# BBBBoat-cape.net
KiCad netlist of a schematic drawn in EAGLE
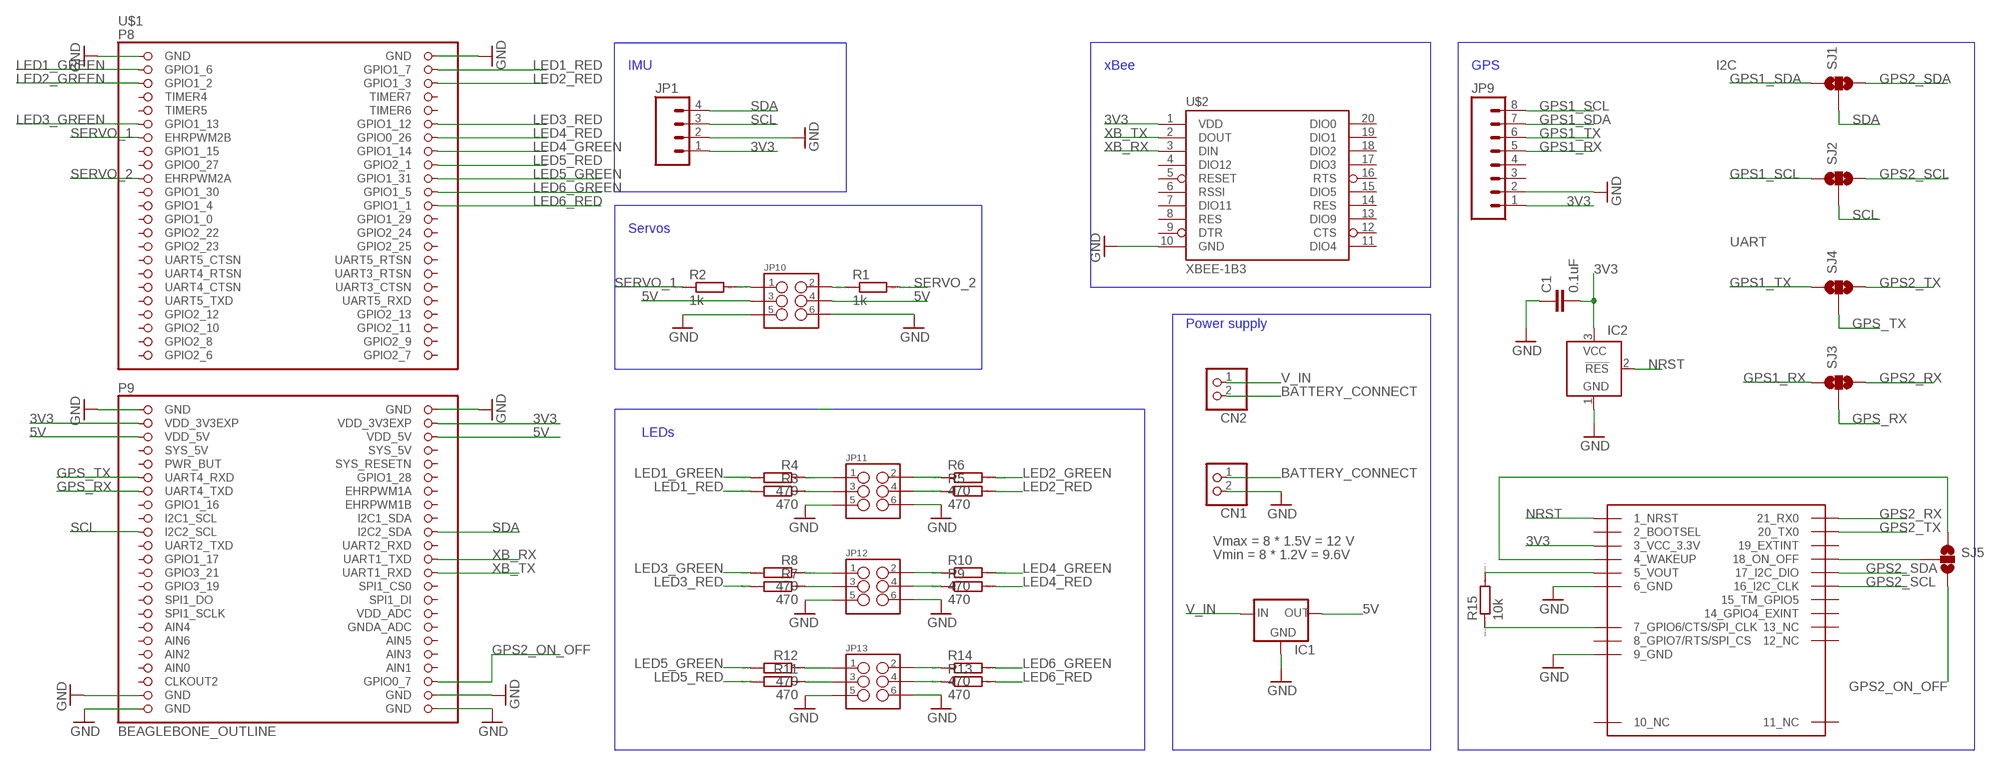
[diagram p0: schematic, sheet 1]

(export (version "E")
  (design (tool "Eeschema 10.0.6"))
  (components
    (comp (ref "C1")
      (value "0.1uF")
      (footprint "eagle-import:0603-CAP")
      (libsource (lib "eagle-import") (part "0.1UF-25V-5%(0603)"))
    )
    (comp (ref "CN1")
      (value "JST_2PIN-SMT")
      (footprint "eagle-import:JST-PH-2-SMT")
      (libsource (lib "eagle-import") (part "JST_2PIN-SMT"))
    )
    (comp (ref "CN2")
      (value "JST_2PIN-SMT")
      (footprint "eagle-import:JST-PH-2-SMT")
      (libsource (lib "eagle-import") (part "JST_2PIN-SMT"))
    )
    (comp (ref "IC1")
      (value "V_REG_78XX-TO-220")
      (footprint "eagle-import:TO-220-ALT")
      (libsource (lib "eagle-import") (part "V_REG_78XX-TO-220"))
    )
    (comp (ref "IC2")
      (value "TCM809")
      (footprint "eagle-import:SOT23B-3")
      (fields (field (name "MF") "MICROCHIP") (field (name "MPN") "TCM809MENB713"))
      (libsource (lib "eagle-import") (part "TCM809"))
    )
    (comp (ref "JP1")
      (value "M04SMD_STRAIGHT_COMBO")
      (footprint "eagle-import:1X04_SMD_STRAIGHT_COMBO")
      (libsource (lib "eagle-import") (part "M04SMD_STRAIGHT_COMBO"))
    )
    (comp (ref "JP9")
      (value "M08SMD-MALE")
      (footprint "eagle-import:1X08_SMD_MALE")
      (libsource (lib "eagle-import") (part "M08SMD-MALE"))
    )
    (comp (ref "JP10")
      (value "M03X2")
      (footprint "eagle-import:2X3_SMD")
      (libsource (lib "eagle-import") (part "M03X2"))
    )
    (comp (ref "JP11")
      (value "M03X2")
      (footprint "eagle-import:2X3_SMD")
      (libsource (lib "eagle-import") (part "M03X2"))
    )
    (comp (ref "JP12")
      (value "M03X2")
      (footprint "eagle-import:2X3_SMD")
      (libsource (lib "eagle-import") (part "M03X2"))
    )
    (comp (ref "JP13")
      (value "M03X2")
      (footprint "eagle-import:2X3_SMD")
      (libsource (lib "eagle-import") (part "M03X2"))
    )
    (comp (ref "R1")
      (value "1k")
      (footprint "eagle-import:0204_7")
      (libsource (lib "eagle-import") (part "R0204/7"))
    )
    (comp (ref "R2")
      (value "1k")
      (footprint "eagle-import:0204_7")
      (libsource (lib "eagle-import") (part "R0204/7"))
    )
    (comp (ref "R3")
      (value "470")
      (footprint "eagle-import:0204_7")
      (libsource (lib "eagle-import") (part "R0204/7"))
    )
    (comp (ref "R4")
      (value "470")
      (footprint "eagle-import:0204_7")
      (libsource (lib "eagle-import") (part "R0204/7"))
    )
    (comp (ref "R5")
      (value "470")
      (footprint "eagle-import:0204_7")
      (libsource (lib "eagle-import") (part "R0204/7"))
    )
    (comp (ref "R6")
      (value "470")
      (footprint "eagle-import:0204_7")
      (libsource (lib "eagle-import") (part "R0204/7"))
    )
    (comp (ref "R7")
      (value "470")
      (footprint "eagle-import:0204_7")
      (libsource (lib "eagle-import") (part "R0204/7"))
    )
    (comp (ref "R8")
      (value "470")
      (footprint "eagle-import:0204_7")
      (libsource (lib "eagle-import") (part "R0204/7"))
    )
    (comp (ref "R9")
      (value "470")
      (footprint "eagle-import:0204_7")
      (libsource (lib "eagle-import") (part "R0204/7"))
    )
    (comp (ref "R10")
      (value "470")
      (footprint "eagle-import:0204_7")
      (libsource (lib "eagle-import") (part "R0204/7"))
    )
    (comp (ref "R11")
      (value "470")
      (footprint "eagle-import:0204_7")
      (libsource (lib "eagle-import") (part "R0204/7"))
    )
    (comp (ref "R12")
      (value "470")
      (footprint "eagle-import:0204_7")
      (libsource (lib "eagle-import") (part "R0204/7"))
    )
    (comp (ref "R13")
      (value "470")
      (footprint "eagle-import:0204_7")
      (libsource (lib "eagle-import") (part "R0204/7"))
    )
    (comp (ref "R14")
      (value "470")
      (footprint "eagle-import:0204_7")
      (libsource (lib "eagle-import") (part "R0204/7"))
    )
    (comp (ref "R15")
      (value "10k")
      (footprint "eagle-import:0204_7")
      (libsource (lib "eagle-import") (part "R0204/7"))
    )
    (comp (ref "SJ1")
      (value "SOLDERJUMPER_2WAYT")
      (footprint "eagle-import:SJ_2")
      (libsource (lib "eagle-import") (part "SOLDERJUMPER_2WAYT"))
    )
    (comp (ref "SJ2")
      (value "SOLDERJUMPER_2WAYT")
      (footprint "eagle-import:SJ_2")
      (libsource (lib "eagle-import") (part "SOLDERJUMPER_2WAYT"))
    )
    (comp (ref "SJ3")
      (value "SOLDERJUMPER_2WAYT")
      (footprint "eagle-import:SJ_2")
      (libsource (lib "eagle-import") (part "SOLDERJUMPER_2WAYT"))
    )
    (comp (ref "SJ4")
      (value "SOLDERJUMPER_2WAYT")
      (footprint "eagle-import:SJ_2")
      (libsource (lib "eagle-import") (part "SOLDERJUMPER_2WAYT"))
    )
    (comp (ref "SJ5")
      (value "SOLDERJUMPER_2WAYT")
      (footprint "eagle-import:SJ_2")
      (libsource (lib "eagle-import") (part "SOLDERJUMPER_2WAYT"))
    )
    (comp (ref "U$1")
      (value "BEAGLEBONE_OUTLINE")
      (footprint "eagle-import:BEAGLEBONE_SHIELD")
      (libsource (lib "eagle-import") (part "BEAGLEBONE_OUTLINE"))
    )
    (comp (ref "U$2")
      (value "XBEE-1B3")
      (footprint "eagle-import:XBEE-SMD")
      (libsource (lib "eagle-import") (part "XBEE-1B3"))
    )
    (comp (ref "U$3")
      (value "A2035-H")
      (footprint "eagle-import:A2035H")
      (libsource (lib "eagle-import") (part "A2035-H"))
    )
  )
  (nets
    (net (code "1") (name "/3V3") (class "Default")
      (node (ref "C1") (pin "2") (pinfunction "2_2") (pintype "passive"))
      (node (ref "IC2") (pin "3") (pinfunction "VCC_3") (pintype "power_in"))
      (node (ref "JP1") (pin "1") (pinfunction "1_1") (pintype "passive"))
      (node (ref "JP9") (pin "1") (pinfunction "1_1") (pintype "passive"))
      (node (ref "U$1") (pin "49") (pinfunction "VDD_3V3EXP_49") (pintype "power_in"))
      (node (ref "U$1") (pin "50") (pinfunction "VDD_3V3EXP_50") (pintype "power_in"))
      (node (ref "U$2") (pin "1") (pinfunction "VDD_1") (pintype "power_in"))
      (node (ref "U$3") (pin "3_VCC_3.3V") (pinfunction "3_VCC_3.3V_3_VCC_3.3V") (pintype "bidirectional"))
    )
    (net (code "2") (name "/5V") (class "Default")
      (node (ref "IC1") (pin "OUT") (pinfunction "OUT_OUT") (pintype "output"))
      (node (ref "JP10") (pin "3") (pinfunction "3_3") (pintype "bidirectional"))
      (node (ref "JP10") (pin "4") (pinfunction "4_4") (pintype "bidirectional"))
      (node (ref "U$1") (pin "51") (pinfunction "VDD_5V_51") (pintype "power_in"))
      (node (ref "U$1") (pin "52") (pinfunction "VDD_5V_52") (pintype "power_in"))
    )
    (net (code "3") (name "/AIN0") (class "Default")
      (node (ref "U$1") (pin "85") (pinfunction "AIN0_85") (pintype "power_in"))
    )
    (net (code "4") (name "/BATTERY_CONNECT") (class "Default")
      (node (ref "CN1") (pin "1") (pinfunction "2_1") (pintype "passive"))
      (node (ref "CN2") (pin "2") (pinfunction "1_2") (pintype "passive"))
    )
    (net (code "5") (name "/GPS1_RX") (class "Default")
      (node (ref "JP9") (pin "5") (pinfunction "5_5") (pintype "passive"))
      (node (ref "SJ3") (pin "1") (pinfunction "1_1") (pintype "passive"))
    )
    (net (code "6") (name "/GPS1_SCL") (class "Default")
      (node (ref "JP9") (pin "8") (pinfunction "8_8") (pintype "passive"))
      (node (ref "SJ2") (pin "1") (pinfunction "1_1") (pintype "passive"))
    )
    (net (code "7") (name "/GPS1_SDA") (class "Default")
      (node (ref "JP9") (pin "7") (pinfunction "7_7") (pintype "passive"))
      (node (ref "SJ1") (pin "1") (pinfunction "1_1") (pintype "passive"))
    )
    (net (code "8") (name "/GPS1_TX") (class "Default")
      (node (ref "JP9") (pin "6") (pinfunction "6_6") (pintype "passive"))
      (node (ref "SJ4") (pin "1") (pinfunction "1_1") (pintype "passive"))
    )
    (net (code "9") (name "/GPS2_ON_OFF") (class "Default")
      (node (ref "SJ5") (pin "3") (pinfunction "3_3") (pintype "passive"))
      (node (ref "U$1") (pin "88") (pinfunction "GPIO0_7_88") (pintype "passive"))
    )
    (net (code "10") (name "/GPS2_RX") (class "Default")
      (node (ref "SJ3") (pin "3") (pinfunction "3_3") (pintype "passive"))
      (node (ref "U$3") (pin "21_RX0") (pinfunction "21_RX0_21_RX0") (pintype "bidirectional"))
    )
    (net (code "11") (name "/GPS2_SCL") (class "Default")
      (node (ref "SJ2") (pin "3") (pinfunction "3_3") (pintype "passive"))
      (node (ref "U$3") (pin "16_I2C_CLK") (pinfunction "16_I2C_CLK_16_I2C_CLK") (pintype "bidirectional"))
    )
    (net (code "12") (name "/GPS2_SDA") (class "Default")
      (node (ref "SJ1") (pin "3") (pinfunction "3_3") (pintype "passive"))
      (node (ref "U$3") (pin "17_I2C_DIO") (pinfunction "17_I2C_DIO_17_I2C_DIO") (pintype "bidirectional"))
    )
    (net (code "13") (name "/GPS2_TX") (class "Default")
      (node (ref "SJ4") (pin "3") (pinfunction "3_3") (pintype "passive"))
      (node (ref "U$3") (pin "20_TX0") (pinfunction "20_TX0_20_TX0") (pintype "bidirectional"))
    )
    (net (code "14") (name "/GPS_RX") (class "Default")
      (node (ref "SJ3") (pin "2") (pinfunction "2_2") (pintype "passive"))
      (node (ref "U$1") (pin "59") (pinfunction "UART4_TXD_59") (pintype "passive"))
    )
    (net (code "15") (name "/GPS_TX") (class "Default")
      (node (ref "SJ4") (pin "2") (pinfunction "2_2") (pintype "passive"))
      (node (ref "U$1") (pin "57") (pinfunction "UART4_RXD_57") (pintype "passive"))
    )
    (net (code "16") (name "/LED1_GREEN") (class "Default")
      (node (ref "R4") (pin "2") (pinfunction "2_2") (pintype "passive"))
      (node (ref "U$1") (pin "3") (pinfunction "GPIO1_6_3") (pintype "passive"))
    )
    (net (code "17") (name "/LED1_RED") (class "Default")
      (node (ref "R3") (pin "2") (pinfunction "2_2") (pintype "passive"))
      (node (ref "U$1") (pin "4") (pinfunction "GPIO1_7_4") (pintype "passive"))
    )
    (net (code "18") (name "/LED2_GREEN") (class "Default")
      (node (ref "R6") (pin "2") (pinfunction "2_2") (pintype "passive"))
      (node (ref "U$1") (pin "5") (pinfunction "GPIO1_2_5") (pintype "passive"))
    )
    (net (code "19") (name "/LED2_RED") (class "Default")
      (node (ref "R5") (pin "2") (pinfunction "2_2") (pintype "passive"))
      (node (ref "U$1") (pin "6") (pinfunction "GPIO1_3_6") (pintype "passive"))
    )
    (net (code "20") (name "/LED3_GREEN") (class "Default")
      (node (ref "R8") (pin "2") (pinfunction "2_2") (pintype "passive"))
      (node (ref "U$1") (pin "11") (pinfunction "GPIO1_13_11") (pintype "passive"))
    )
    (net (code "21") (name "/LED3_RED") (class "Default")
      (node (ref "R7") (pin "2") (pinfunction "2_2") (pintype "passive"))
      (node (ref "U$1") (pin "12") (pinfunction "GPIO1_12_12") (pintype "passive"))
    )
    (net (code "22") (name "/LED4_GREEN") (class "Default")
      (node (ref "R10") (pin "2") (pinfunction "2_2") (pintype "passive"))
      (node (ref "U$1") (pin "16") (pinfunction "GPIO1_14_16") (pintype "passive"))
    )
    (net (code "23") (name "/LED4_RED") (class "Default")
      (node (ref "R9") (pin "2") (pinfunction "2_2") (pintype "passive"))
      (node (ref "U$1") (pin "14") (pinfunction "GPIO0_26_14") (pintype "passive"))
    )
    (net (code "24") (name "/LED5_GREEN") (class "Default")
      (node (ref "R12") (pin "2") (pinfunction "2_2") (pintype "passive"))
      (node (ref "U$1") (pin "20") (pinfunction "GPIO1_31_20") (pintype "passive"))
    )
    (net (code "25") (name "/LED5_RED") (class "Default")
      (node (ref "R11") (pin "2") (pinfunction "2_2") (pintype "passive"))
      (node (ref "U$1") (pin "18") (pinfunction "GPIO2_1_18") (pintype "passive"))
    )
    (net (code "26") (name "/LED6_GREEN") (class "Default")
      (node (ref "R14") (pin "2") (pinfunction "2_2") (pintype "passive"))
      (node (ref "U$1") (pin "22") (pinfunction "GPIO1_5_22") (pintype "passive"))
    )
    (net (code "27") (name "/LED6_RED") (class "Default")
      (node (ref "R13") (pin "2") (pinfunction "2_2") (pintype "passive"))
      (node (ref "U$1") (pin "24") (pinfunction "GPIO1_1_24") (pintype "passive"))
    )
    (net (code "28") (name "/NRST") (class "Default")
      (node (ref "IC2") (pin "2") (pinfunction "~{RES}_2") (pintype "output"))
      (node (ref "U$3") (pin "1_NRST") (pinfunction "1_NRST_1_NRST") (pintype "bidirectional"))
    )
    (net (code "29") (name "/SCL") (class "Default")
      (node (ref "JP1") (pin "3") (pinfunction "3_3") (pintype "passive"))
      (node (ref "SJ2") (pin "2") (pinfunction "2_2") (pintype "passive"))
      (node (ref "U$1") (pin "65") (pinfunction "I2C2_SCL_65") (pintype "passive"))
    )
    (net (code "30") (name "/SDA") (class "Default")
      (node (ref "JP1") (pin "4") (pinfunction "4_4") (pintype "passive"))
      (node (ref "SJ1") (pin "2") (pinfunction "2_2") (pintype "passive"))
      (node (ref "U$1") (pin "66") (pinfunction "I2C2_SDA_66") (pintype "passive"))
    )
    (net (code "31") (name "/SERVO_1") (class "Default")
      (node (ref "R2") (pin "1") (pinfunction "1_1") (pintype "passive"))
      (node (ref "U$1") (pin "13") (pinfunction "EHRPWM2B_13") (pintype "passive"))
    )
    (net (code "32") (name "/SERVO_2") (class "Default")
      (node (ref "R1") (pin "2") (pinfunction "2_2") (pintype "passive"))
      (node (ref "U$1") (pin "19") (pinfunction "EHRPWM2A_19") (pintype "passive"))
    )
    (net (code "33") (name "/SYS_5V") (class "Default")
      (node (ref "U$1") (pin "53") (pinfunction "SYS_5V_53") (pintype "power_in"))
    )
    (net (code "34") (name "/V_IN") (class "Default")
      (node (ref "CN2") (pin "1") (pinfunction "2_1") (pintype "passive"))
      (node (ref "IC1") (pin "IN") (pinfunction "IN_IN") (pintype "input"))
    )
    (net (code "35") (name "/XB_RX") (class "Default")
      (node (ref "U$1") (pin "70") (pinfunction "UART1_TXD_70") (pintype "passive"))
      (node (ref "U$2") (pin "3") (pinfunction "DIN_3") (pintype "input"))
    )
    (net (code "36") (name "/XB_TX") (class "Default")
      (node (ref "U$1") (pin "72") (pinfunction "UART1_RXD_72") (pintype "passive"))
      (node (ref "U$2") (pin "2") (pinfunction "DOUT_2") (pintype "output"))
    )
    (net (code "37") (name "GND") (class "Default")
      (node (ref "C1") (pin "1") (pinfunction "1_1") (pintype "passive"))
      (node (ref "CN1") (pin "2") (pinfunction "1_2") (pintype "passive"))
      (node (ref "IC1") (pin "GND") (pinfunction "GND_GND") (pintype "input"))
      (node (ref "IC2") (pin "1") (pinfunction "GND_1") (pintype "power_in"))
      (node (ref "JP1") (pin "2") (pinfunction "2_2") (pintype "passive"))
      (node (ref "JP10") (pin "5") (pinfunction "5_5") (pintype "bidirectional"))
      (node (ref "JP10") (pin "6") (pinfunction "6_6") (pintype "bidirectional"))
      (node (ref "JP11") (pin "5") (pinfunction "5_5") (pintype "bidirectional"))
      (node (ref "JP11") (pin "6") (pinfunction "6_6") (pintype "bidirectional"))
      (node (ref "JP12") (pin "5") (pinfunction "5_5") (pintype "bidirectional"))
      (node (ref "JP12") (pin "6") (pinfunction "6_6") (pintype "bidirectional"))
      (node (ref "JP13") (pin "5") (pinfunction "5_5") (pintype "bidirectional"))
      (node (ref "JP13") (pin "6") (pinfunction "6_6") (pintype "bidirectional"))
      (node (ref "JP9") (pin "2") (pinfunction "2_2") (pintype "passive"))
      (node (ref "U$1") (pin "1") (pinfunction "GND_1") (pintype "power_in"))
      (node (ref "U$1") (pin "2") (pinfunction "GND_2") (pintype "power_in"))
      (node (ref "U$1") (pin "47") (pinfunction "GND_47") (pintype "power_in"))
      (node (ref "U$1") (pin "48") (pinfunction "GND_48") (pintype "power_in"))
      (node (ref "U$1") (pin "89") (pinfunction "GND_89") (pintype "power_in"))
      (node (ref "U$1") (pin "90") (pinfunction "GND_90") (pintype "power_in"))
      (node (ref "U$1") (pin "91") (pinfunction "GND_91") (pintype "power_in"))
      (node (ref "U$1") (pin "92") (pinfunction "GND_92") (pintype "power_in"))
      (node (ref "U$2") (pin "10") (pinfunction "GND_10") (pintype "power_in"))
      (node (ref "U$3") (pin "6_GND") (pinfunction "6_GND_6_GND") (pintype "bidirectional"))
      (node (ref "U$3") (pin "9_GND") (pinfunction "9_GND_9_GND") (pintype "bidirectional"))
    )
    (net (code "38") (name "Net-(JP10-Pad1)") (class "Default")
      (node (ref "JP10") (pin "1") (pinfunction "1_1") (pintype "bidirectional"))
      (node (ref "R2") (pin "2") (pinfunction "2_2") (pintype "passive"))
    )
    (net (code "39") (name "Net-(JP10-Pad2)") (class "Default")
      (node (ref "JP10") (pin "2") (pinfunction "2_2") (pintype "bidirectional"))
      (node (ref "R1") (pin "1") (pinfunction "1_1") (pintype "passive"))
    )
    (net (code "40") (name "Net-(JP11-Pad1)") (class "Default")
      (node (ref "JP11") (pin "1") (pinfunction "1_1") (pintype "bidirectional"))
      (node (ref "R4") (pin "1") (pinfunction "1_1") (pintype "passive"))
    )
    (net (code "41") (name "Net-(JP11-Pad2)") (class "Default")
      (node (ref "JP11") (pin "2") (pinfunction "2_2") (pintype "bidirectional"))
      (node (ref "R6") (pin "1") (pinfunction "1_1") (pintype "passive"))
    )
    (net (code "42") (name "Net-(JP11-Pad3)") (class "Default")
      (node (ref "JP11") (pin "3") (pinfunction "3_3") (pintype "bidirectional"))
      (node (ref "R3") (pin "1") (pinfunction "1_1") (pintype "passive"))
    )
    (net (code "43") (name "Net-(JP11-Pad4)") (class "Default")
      (node (ref "JP11") (pin "4") (pinfunction "4_4") (pintype "bidirectional"))
      (node (ref "R5") (pin "1") (pinfunction "1_1") (pintype "passive"))
    )
    (net (code "44") (name "Net-(JP12-Pad1)") (class "Default")
      (node (ref "JP12") (pin "1") (pinfunction "1_1") (pintype "bidirectional"))
      (node (ref "R8") (pin "1") (pinfunction "1_1") (pintype "passive"))
    )
    (net (code "45") (name "Net-(JP12-Pad2)") (class "Default")
      (node (ref "JP12") (pin "2") (pinfunction "2_2") (pintype "bidirectional"))
      (node (ref "R10") (pin "1") (pinfunction "1_1") (pintype "passive"))
    )
    (net (code "46") (name "Net-(JP12-Pad3)") (class "Default")
      (node (ref "JP12") (pin "3") (pinfunction "3_3") (pintype "bidirectional"))
      (node (ref "R7") (pin "1") (pinfunction "1_1") (pintype "passive"))
    )
    (net (code "47") (name "Net-(JP12-Pad4)") (class "Default")
      (node (ref "JP12") (pin "4") (pinfunction "4_4") (pintype "bidirectional"))
      (node (ref "R9") (pin "1") (pinfunction "1_1") (pintype "passive"))
    )
    (net (code "48") (name "Net-(JP13-Pad1)") (class "Default")
      (node (ref "JP13") (pin "1") (pinfunction "1_1") (pintype "bidirectional"))
      (node (ref "R12") (pin "1") (pinfunction "1_1") (pintype "passive"))
    )
    (net (code "49") (name "Net-(JP13-Pad2)") (class "Default")
      (node (ref "JP13") (pin "2") (pinfunction "2_2") (pintype "bidirectional"))
      (node (ref "R14") (pin "1") (pinfunction "1_1") (pintype "passive"))
    )
    (net (code "50") (name "Net-(JP13-Pad3)") (class "Default")
      (node (ref "JP13") (pin "3") (pinfunction "3_3") (pintype "bidirectional"))
      (node (ref "R11") (pin "1") (pinfunction "1_1") (pintype "passive"))
    )
    (net (code "51") (name "Net-(JP13-Pad4)") (class "Default")
      (node (ref "JP13") (pin "4") (pinfunction "4_4") (pintype "bidirectional"))
      (node (ref "R13") (pin "1") (pinfunction "1_1") (pintype "passive"))
    )
    (net (code "52") (name "Net-(R15-Pad1)") (class "Default")
      (node (ref "R15") (pin "1") (pinfunction "1_1") (pintype "passive"))
      (node (ref "U$3") (pin "7_GPIO6/CTS/SPI_CLK") (pinfunction "7_GPIO6/CTS/SPI_CLK_7_GPIO6/CTS/SPI_CLK") (pintype "bidirectional"))
    )
    (net (code "53") (name "Net-(R15-Pad2)") (class "Default")
      (node (ref "R15") (pin "2") (pinfunction "2_2") (pintype "passive"))
      (node (ref "U$3") (pin "5_VOUT") (pinfunction "5_VOUT_5_VOUT") (pintype "bidirectional"))
    )
    (net (code "54") (name "Net-(SJ5-Pad1)") (class "Default")
      (node (ref "SJ5") (pin "1") (pinfunction "1_1") (pintype "passive"))
      (node (ref "U$3") (pin "4_WAKEUP") (pinfunction "4_WAKEUP_4_WAKEUP") (pintype "bidirectional"))
    )
    (net (code "55") (name "Net-(SJ5-Pad2)") (class "Default")
      (node (ref "SJ5") (pin "2") (pinfunction "2_2") (pintype "passive"))
      (node (ref "U$3") (pin "18_ON_OFF") (pinfunction "18_ON_OFF_18_ON_OFF") (pintype "bidirectional"))
    )
    (net (code "56") (name "unconnected-(JP9-Pad3)") (class "Default")
      (node (ref "JP9") (pin "3") (pinfunction "3_3") (pintype "passive"))
    )
    (net (code "57") (name "unconnected-(JP9-Pad4)") (class "Default")
      (node (ref "JP9") (pin "4") (pinfunction "4_4") (pintype "passive"))
    )
    (net (code "58") (name "unconnected-(U$1-AIN1-Pad86)") (class "Default")
      (node (ref "U$1") (pin "86") (pinfunction "AIN1_86") (pintype "passive"))
    )
    (net (code "59") (name "unconnected-(U$1-AIN2-Pad83)") (class "Default")
      (node (ref "U$1") (pin "83") (pinfunction "AIN2_83") (pintype "passive"))
    )
    (net (code "60") (name "unconnected-(U$1-AIN3-Pad84)") (class "Default")
      (node (ref "U$1") (pin "84") (pinfunction "AIN3_84") (pintype "passive"))
    )
    (net (code "61") (name "unconnected-(U$1-AIN4-Pad79)") (class "Default")
      (node (ref "U$1") (pin "79") (pinfunction "AIN4_79") (pintype "passive"))
    )
    (net (code "62") (name "unconnected-(U$1-AIN5-Pad82)") (class "Default")
      (node (ref "U$1") (pin "82") (pinfunction "AIN5_82") (pintype "passive"))
    )
    (net (code "63") (name "unconnected-(U$1-AIN6-Pad81)") (class "Default")
      (node (ref "U$1") (pin "81") (pinfunction "AIN6_81") (pintype "passive"))
    )
    (net (code "64") (name "unconnected-(U$1-CLKOUT2-Pad87)") (class "Default")
      (node (ref "U$1") (pin "87") (pinfunction "CLKOUT2_87") (pintype "input"))
    )
    (net (code "65") (name "unconnected-(U$1-EHRPWM1A-Pad60)") (class "Default")
      (node (ref "U$1") (pin "60") (pinfunction "EHRPWM1A_60") (pintype "passive"))
    )
    (net (code "66") (name "unconnected-(U$1-EHRPWM1B-Pad62)") (class "Default")
      (node (ref "U$1") (pin "62") (pinfunction "EHRPWM1B_62") (pintype "passive"))
    )
    (net (code "67") (name "unconnected-(U$1-GNDA_ADC-Pad80)") (class "Default")
      (node (ref "U$1") (pin "80") (pinfunction "GNDA_ADC_80") (pintype "passive"))
    )
    (net (code "68") (name "unconnected-(U$1-GPIO0_27-Pad17)") (class "Default")
      (node (ref "U$1") (pin "17") (pinfunction "GPIO0_27_17") (pintype "passive"))
    )
    (net (code "69") (name "unconnected-(U$1-GPIO1_0-Pad25)") (class "Default")
      (node (ref "U$1") (pin "25") (pinfunction "GPIO1_0_25") (pintype "passive"))
    )
    (net (code "70") (name "unconnected-(U$1-GPIO1_4-Pad23)") (class "Default")
      (node (ref "U$1") (pin "23") (pinfunction "GPIO1_4_23") (pintype "passive"))
    )
    (net (code "71") (name "unconnected-(U$1-GPIO1_15-Pad15)") (class "Default")
      (node (ref "U$1") (pin "15") (pinfunction "GPIO1_15_15") (pintype "passive"))
    )
    (net (code "72") (name "unconnected-(U$1-GPIO1_16-Pad61)") (class "Default")
      (node (ref "U$1") (pin "61") (pinfunction "GPIO1_16_61") (pintype "passive"))
    )
    (net (code "73") (name "unconnected-(U$1-GPIO1_17-Pad69)") (class "Default")
      (node (ref "U$1") (pin "69") (pinfunction "GPIO1_17_69") (pintype "passive"))
    )
    (net (code "74") (name "unconnected-(U$1-GPIO1_28-Pad58)") (class "Default")
      (node (ref "U$1") (pin "58") (pinfunction "GPIO1_28_58") (pintype "passive"))
    )
    (net (code "75") (name "unconnected-(U$1-GPIO1_29-Pad26)") (class "Default")
      (node (ref "U$1") (pin "26") (pinfunction "GPIO1_29_26") (pintype "passive"))
    )
    (net (code "76") (name "unconnected-(U$1-GPIO1_30-Pad21)") (class "Default")
      (node (ref "U$1") (pin "21") (pinfunction "GPIO1_30_21") (pintype "passive"))
    )
    (net (code "77") (name "unconnected-(U$1-GPIO2_6-Pad45)") (class "Default")
      (node (ref "U$1") (pin "45") (pinfunction "GPIO2_6_45") (pintype "passive"))
    )
    (net (code "78") (name "unconnected-(U$1-GPIO2_7-Pad46)") (class "Default")
      (node (ref "U$1") (pin "46") (pinfunction "GPIO2_7_46") (pintype "passive"))
    )
    (net (code "79") (name "unconnected-(U$1-GPIO2_8-Pad43)") (class "Default")
      (node (ref "U$1") (pin "43") (pinfunction "GPIO2_8_43") (pintype "passive"))
    )
    (net (code "80") (name "unconnected-(U$1-GPIO2_9-Pad44)") (class "Default")
      (node (ref "U$1") (pin "44") (pinfunction "GPIO2_9_44") (pintype "passive"))
    )
    (net (code "81") (name "unconnected-(U$1-GPIO2_10-Pad41)") (class "Default")
      (node (ref "U$1") (pin "41") (pinfunction "GPIO2_10_41") (pintype "passive"))
    )
    (net (code "82") (name "unconnected-(U$1-GPIO2_11-Pad42)") (class "Default")
      (node (ref "U$1") (pin "42") (pinfunction "GPIO2_11_42") (pintype "passive"))
    )
    (net (code "83") (name "unconnected-(U$1-GPIO2_12-Pad39)") (class "Default")
      (node (ref "U$1") (pin "39") (pinfunction "GPIO2_12_39") (pintype "passive"))
    )
    (net (code "84") (name "unconnected-(U$1-GPIO2_13-Pad40)") (class "Default")
      (node (ref "U$1") (pin "40") (pinfunction "GPIO2_13_40") (pintype "passive"))
    )
    (net (code "85") (name "unconnected-(U$1-GPIO2_22-Pad27)") (class "Default")
      (node (ref "U$1") (pin "27") (pinfunction "GPIO2_22_27") (pintype "passive"))
    )
    (net (code "86") (name "unconnected-(U$1-GPIO2_23-Pad29)") (class "Default")
      (node (ref "U$1") (pin "29") (pinfunction "GPIO2_23_29") (pintype "passive"))
    )
    (net (code "87") (name "unconnected-(U$1-GPIO2_24-Pad28)") (class "Default")
      (node (ref "U$1") (pin "28") (pinfunction "GPIO2_24_28") (pintype "passive"))
    )
    (net (code "88") (name "unconnected-(U$1-GPIO2_25-Pad30)") (class "Default")
      (node (ref "U$1") (pin "30") (pinfunction "GPIO2_25_30") (pintype "passive"))
    )
    (net (code "89") (name "unconnected-(U$1-GPIO3_19-Pad73)") (class "Default")
      (node (ref "U$1") (pin "73") (pinfunction "GPIO3_19_73") (pintype "passive"))
    )
    (net (code "90") (name "unconnected-(U$1-GPIO3_21-Pad71)") (class "Default")
      (node (ref "U$1") (pin "71") (pinfunction "GPIO3_21_71") (pintype "passive"))
    )
    (net (code "91") (name "unconnected-(U$1-I2C1_SCL-Pad63)") (class "Default")
      (node (ref "U$1") (pin "63") (pinfunction "I2C1_SCL_63") (pintype "passive"))
    )
    (net (code "92") (name "unconnected-(U$1-I2C1_SDA-Pad64)") (class "Default")
      (node (ref "U$1") (pin "64") (pinfunction "I2C1_SDA_64") (pintype "passive"))
    )
    (net (code "93") (name "unconnected-(U$1-PWR_BUT-Pad55)") (class "Default")
      (node (ref "U$1") (pin "55") (pinfunction "PWR_BUT_55") (pintype "passive"))
    )
    (net (code "94") (name "unconnected-(U$1-SPI1_CS0-Pad74)") (class "Default")
      (node (ref "U$1") (pin "74") (pinfunction "SPI1_CS0_74") (pintype "passive"))
    )
    (net (code "95") (name "unconnected-(U$1-SPI1_DI-Pad76)") (class "Default")
      (node (ref "U$1") (pin "76") (pinfunction "SPI1_DI_76") (pintype "passive"))
    )
    (net (code "96") (name "unconnected-(U$1-SPI1_DO-Pad75)") (class "Default")
      (node (ref "U$1") (pin "75") (pinfunction "SPI1_DO_75") (pintype "passive"))
    )
    (net (code "97") (name "unconnected-(U$1-SPI1_SCLK-Pad77)") (class "Default")
      (node (ref "U$1") (pin "77") (pinfunction "SPI1_SCLK_77") (pintype "passive"))
    )
    (net (code "98") (name "unconnected-(U$1-SYS_5V-Pad54)") (class "Default")
      (node (ref "U$1") (pin "54") (pinfunction "SYS_5V_54") (pintype "passive"))
    )
    (net (code "99") (name "unconnected-(U$1-SYS_RESETN-Pad56)") (class "Default")
      (node (ref "U$1") (pin "56") (pinfunction "SYS_RESETN_56") (pintype "passive"))
    )
    (net (code "100") (name "unconnected-(U$1-TIMER4-Pad7)") (class "Default")
      (node (ref "U$1") (pin "7") (pinfunction "TIMER4_7") (pintype "passive"))
    )
    (net (code "101") (name "unconnected-(U$1-TIMER5-Pad9)") (class "Default")
      (node (ref "U$1") (pin "9") (pinfunction "TIMER5_9") (pintype "passive"))
    )
    (net (code "102") (name "unconnected-(U$1-TIMER6-Pad10)") (class "Default")
      (node (ref "U$1") (pin "10") (pinfunction "TIMER6_10") (pintype "passive"))
    )
    (net (code "103") (name "unconnected-(U$1-TIMER7-Pad8)") (class "Default")
      (node (ref "U$1") (pin "8") (pinfunction "TIMER7_8") (pintype "passive"))
    )
    (net (code "104") (name "unconnected-(U$1-UART2_RXD-Pad68)") (class "Default")
      (node (ref "U$1") (pin "68") (pinfunction "UART2_RXD_68") (pintype "passive"))
    )
    (net (code "105") (name "unconnected-(U$1-UART2_TXD-Pad67)") (class "Default")
      (node (ref "U$1") (pin "67") (pinfunction "UART2_TXD_67") (pintype "passive"))
    )
    (net (code "106") (name "unconnected-(U$1-UART3_CTSN-Pad36)") (class "Default")
      (node (ref "U$1") (pin "36") (pinfunction "UART3_CTSN_36") (pintype "passive"))
    )
    (net (code "107") (name "unconnected-(U$1-UART3_RTSN-Pad34)") (class "Default")
      (node (ref "U$1") (pin "34") (pinfunction "UART3_RTSN_34") (pintype "passive"))
    )
    (net (code "108") (name "unconnected-(U$1-UART4_CTSN-Pad35)") (class "Default")
      (node (ref "U$1") (pin "35") (pinfunction "UART4_CTSN_35") (pintype "passive"))
    )
    (net (code "109") (name "unconnected-(U$1-UART4_RTSN-Pad33)") (class "Default")
      (node (ref "U$1") (pin "33") (pinfunction "UART4_RTSN_33") (pintype "passive"))
    )
    (net (code "110") (name "unconnected-(U$1-UART5_CTSN-Pad31)") (class "Default")
      (node (ref "U$1") (pin "31") (pinfunction "UART5_CTSN_31") (pintype "passive"))
    )
    (net (code "111") (name "unconnected-(U$1-UART5_RTSN-Pad32)") (class "Default")
      (node (ref "U$1") (pin "32") (pinfunction "UART5_RTSN_32") (pintype "passive"))
    )
    (net (code "112") (name "unconnected-(U$1-UART5_RXD-Pad38)") (class "Default")
      (node (ref "U$1") (pin "38") (pinfunction "UART5_RXD_38") (pintype "passive"))
    )
    (net (code "113") (name "unconnected-(U$1-UART5_TXD-Pad37)") (class "Default")
      (node (ref "U$1") (pin "37") (pinfunction "UART5_TXD_37") (pintype "passive"))
    )
    (net (code "114") (name "unconnected-(U$1-VDD_ADC-Pad78)") (class "Default")
      (node (ref "U$1") (pin "78") (pinfunction "VDD_ADC_78") (pintype "passive"))
    )
    (net (code "115") (name "unconnected-(U$2-CTS-Pad12)") (class "Default")
      (node (ref "U$2") (pin "12") (pinfunction "CTS_12") (pintype "output"))
    )
    (net (code "116") (name "unconnected-(U$2-DIO0-Pad20)") (class "Default")
      (node (ref "U$2") (pin "20") (pinfunction "DIO0_20") (pintype "bidirectional"))
    )
    (net (code "117") (name "unconnected-(U$2-DIO1-Pad19)") (class "Default")
      (node (ref "U$2") (pin "19") (pinfunction "DIO1_19") (pintype "bidirectional"))
    )
    (net (code "118") (name "unconnected-(U$2-DIO2-Pad18)") (class "Default")
      (node (ref "U$2") (pin "18") (pinfunction "DIO2_18") (pintype "bidirectional"))
    )
    (net (code "119") (name "unconnected-(U$2-DIO3-Pad17)") (class "Default")
      (node (ref "U$2") (pin "17") (pinfunction "DIO3_17") (pintype "bidirectional"))
    )
    (net (code "120") (name "unconnected-(U$2-DIO4-Pad11)") (class "Default")
      (node (ref "U$2") (pin "11") (pinfunction "DIO4_11") (pintype "bidirectional"))
    )
    (net (code "121") (name "unconnected-(U$2-DIO5-Pad15)") (class "Default")
      (node (ref "U$2") (pin "15") (pinfunction "DIO5_15") (pintype "bidirectional"))
    )
    (net (code "122") (name "unconnected-(U$2-DIO9-Pad13)") (class "Default")
      (node (ref "U$2") (pin "13") (pinfunction "DIO9_13") (pintype "bidirectional"))
    )
    (net (code "123") (name "unconnected-(U$2-DIO11-Pad7)") (class "Default")
      (node (ref "U$2") (pin "7") (pinfunction "DIO11_7") (pintype "bidirectional"))
    )
    (net (code "124") (name "unconnected-(U$2-DIO12-Pad4)") (class "Default")
      (node (ref "U$2") (pin "4") (pinfunction "DIO12_4") (pintype "bidirectional"))
    )
    (net (code "125") (name "unconnected-(U$2-DTR-Pad9)") (class "Default")
      (node (ref "U$2") (pin "9") (pinfunction "DTR_9") (pintype "bidirectional"))
    )
    (net (code "126") (name "unconnected-(U$2-RES-Pad8)") (class "Default")
      (node (ref "U$2") (pin "8") (pinfunction "RES_8") (pintype "bidirectional"))
    )
    (net (code "127") (name "unconnected-(U$2-RES-Pad14)") (class "Default")
      (node (ref "U$2") (pin "14") (pinfunction "RES_14") (pintype "bidirectional"))
    )
    (net (code "128") (name "unconnected-(U$2-RESET-Pad5)") (class "Default")
      (node (ref "U$2") (pin "5") (pinfunction "RESET_5") (pintype "input"))
    )
    (net (code "129") (name "unconnected-(U$2-RSSI-Pad6)") (class "Default")
      (node (ref "U$2") (pin "6") (pinfunction "RSSI_6") (pintype "bidirectional"))
    )
    (net (code "130") (name "unconnected-(U$2-RTS-Pad16)") (class "Default")
      (node (ref "U$2") (pin "16") (pinfunction "RTS_16") (pintype "input"))
    )
    (net (code "131") (name "unconnected-(U$3-8_GPIO7{slash}RTS{slash}SPI_CS-Pad8{slash}GPIO7{slash}RTS{slash}SPI_CS)") (class "Default")
      (node (ref "U$3") (pin "8/GPIO7/RTS/SPI_CS") (pinfunction "8_GPIO7/RTS/SPI_CS_8/GPIO7/RTS/SPI_CS") (pintype "bidirectional"))
    )
    (net (code "132") (name "unconnected-(U$3-13_NC-Pad13_GPIO4_EXTINT)") (class "Default")
      (node (ref "U$3") (pin "13_GPIO4_EXTINT") (pinfunction "13_NC_13_GPIO4_EXTINT") (pintype "bidirectional"))
    )
    (net (code "133") (name "unconnected-(U$3-14_GPIO4_EXINT-Pad14_GPIO_EXTINT)") (class "Default")
      (node (ref "U$3") (pin "14_GPIO_EXTINT") (pinfunction "14_GPIO4_EXINT_14_GPIO_EXTINT") (pintype "bidirectional"))
    )
    (net (code "134") (name "unconnected-(U$3-Pad2_BOOTSEL)") (class "Default")
      (node (ref "U$3") (pin "2_BOOTSEL") (pinfunction "2_BOOTSEL_2_BOOTSEL") (pintype "bidirectional"))
    )
    (net (code "135") (name "unconnected-(U$3-Pad10_NC)") (class "Default")
      (node (ref "U$3") (pin "10_NC") (pinfunction "10_NC_10_NC") (pintype "bidirectional"))
    )
    (net (code "136") (name "unconnected-(U$3-Pad11_NC)") (class "Default")
      (node (ref "U$3") (pin "11_NC") (pinfunction "11_NC_11_NC") (pintype "bidirectional"))
    )
    (net (code "137") (name "unconnected-(U$3-Pad12_NC)") (class "Default")
      (node (ref "U$3") (pin "12_NC") (pinfunction "12_NC_12_NC") (pintype "bidirectional"))
    )
    (net (code "138") (name "unconnected-(U$3-Pad15_TM_GPIO5)") (class "Default")
      (node (ref "U$3") (pin "15_TM_GPIO5") (pinfunction "15_TM_GPIO5_15_TM_GPIO5") (pintype "bidirectional"))
    )
    (net (code "139") (name "unconnected-(U$3-Pad19_EXTINT)") (class "Default")
      (node (ref "U$3") (pin "19_EXTINT") (pinfunction "19_EXTINT_19_EXTINT") (pintype "bidirectional"))
    )
  )
)
